# HMTRPBreakoutModule.net
KiCad netlist of a schematic drawn in EAGLE
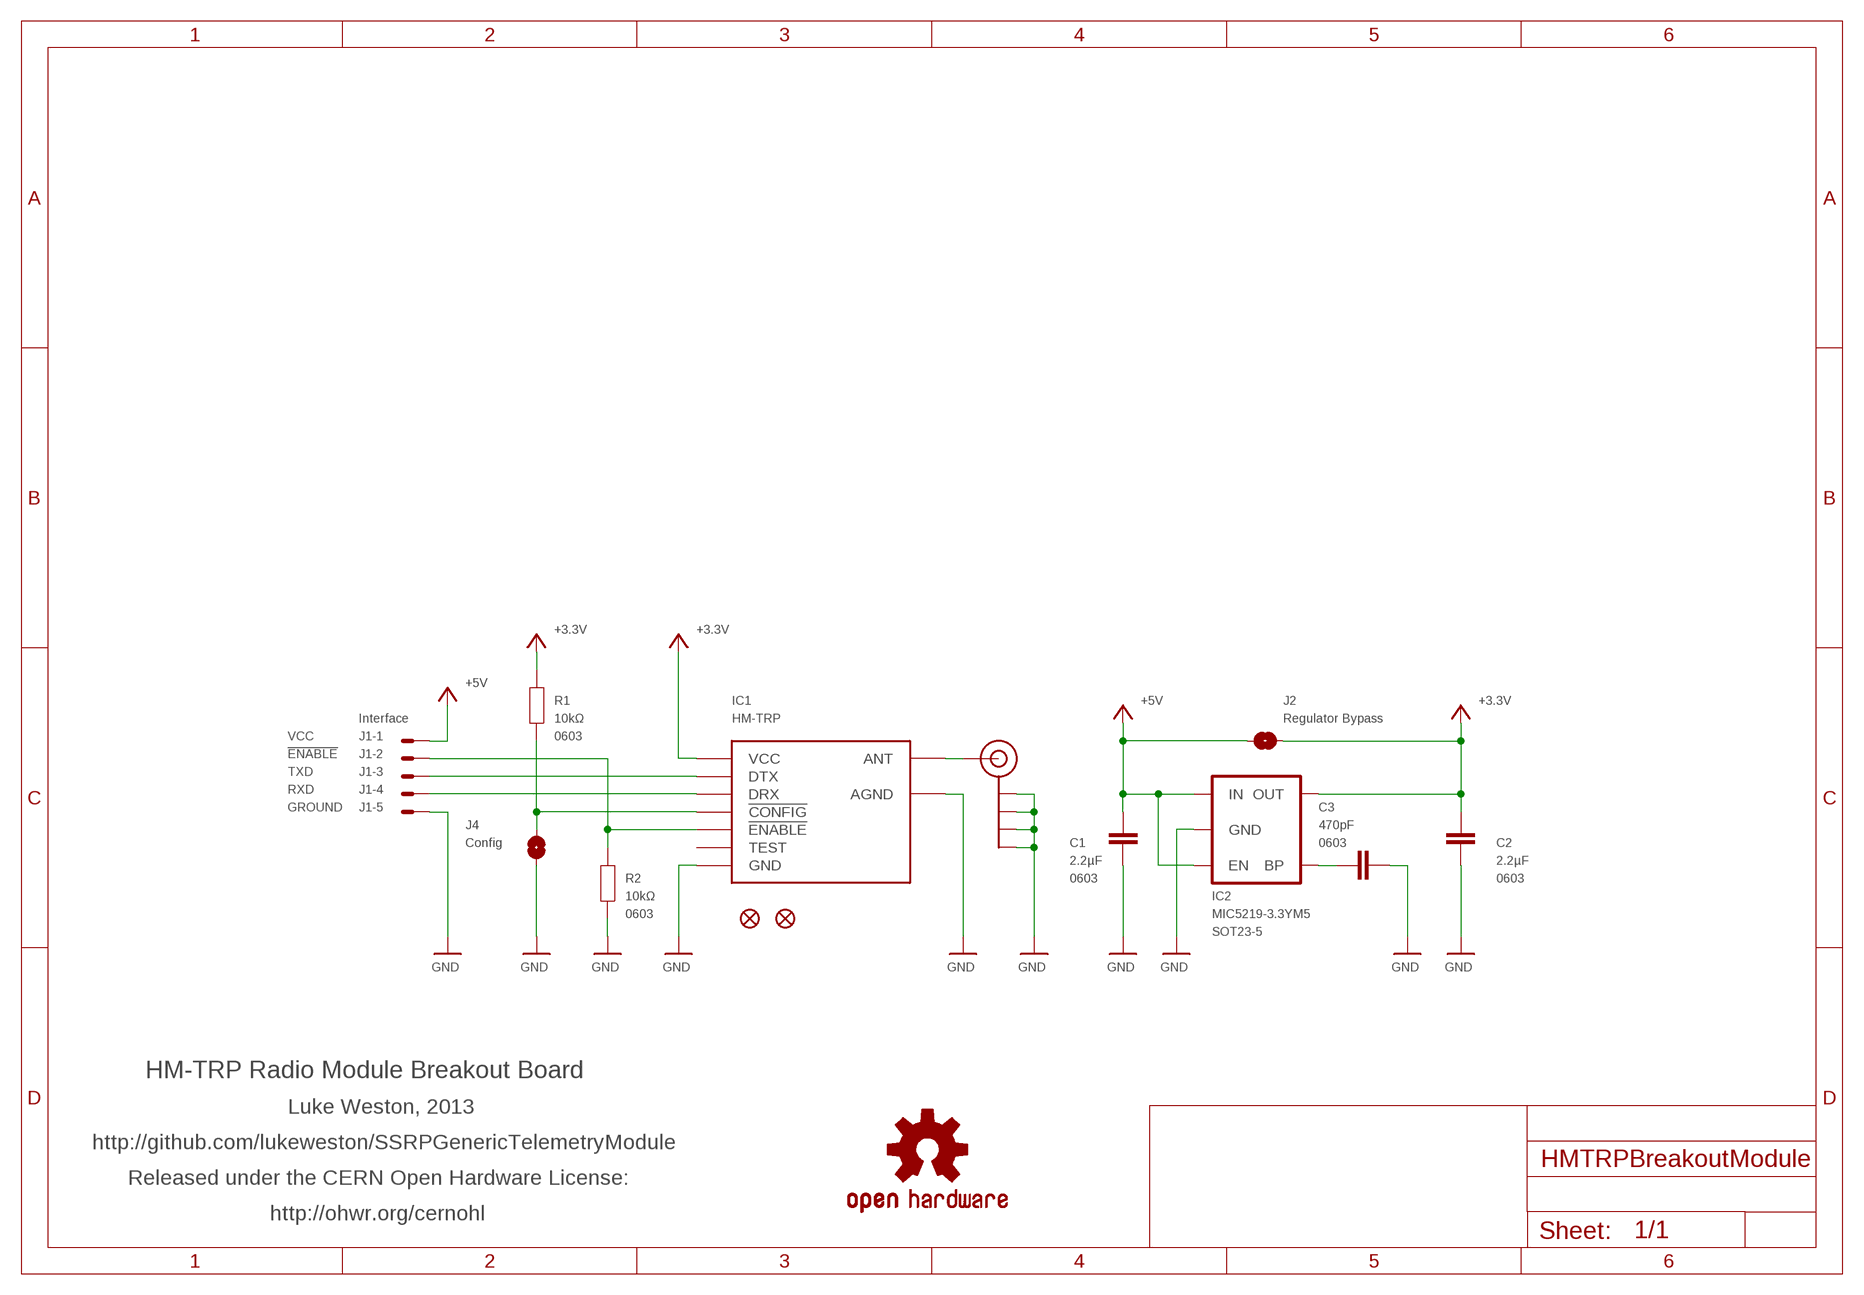
[diagram p0: schematic, sheet 1]

(export (version "E")
  (design (tool "Eeschema 10.0.6"))
  (components
    (comp (ref "C1")
      (value "2.2µF")
      (footprint "eagle-import:0603")
      (fields (field (name "PACKAGE") "0603"))
      (libsource (lib "eagle-import") (part "CAP0603"))
    )
    (comp (ref "C2")
      (value "2.2µF")
      (footprint "eagle-import:0603")
      (fields (field (name "PACKAGE") "0603"))
      (libsource (lib "eagle-import") (part "CAP0603"))
    )
    (comp (ref "C3")
      (value "470pF")
      (footprint "eagle-import:0603")
      (fields (field (name "PACKAGE") "0603"))
      (libsource (lib "eagle-import") (part "CAP0603"))
    )
    (comp (ref "IC1")
      (value "HM-TRP")
      (footprint "eagle-import:HM-TRP-SMD")
      (libsource (lib "eagle-import") (part "HM-TRPSMD"))
    )
    (comp (ref "IC2")
      (value "MIC5219-3.3YM5")
      (footprint "eagle-import:SOT23-5")
      (fields (field (name "PACKAGE") "SOT23-5"))
      (libsource (lib "eagle-import") (part "V_REG_LDOSMD"))
    )
    (comp (ref "J1")
      (value "Interface")
      (footprint "eagle-import:22-23-2051")
      (fields (field (name "MF") "MOLEX") (field (name "MPN") "22-23-2051"))
      (libsource (lib "eagle-import") (part "22-23-2051"))
    )
    (comp (ref "J2")
      (value "Regulator Bypass")
      (footprint "eagle-import:SJ")
      (libsource (lib "eagle-import") (part "SJ"))
    )
    (comp (ref "J3")
      (value "Antenna")
      (footprint "eagle-import:SMA-EDGE")
      (libsource (lib "eagle-import") (part "SMA_EDGE"))
    )
    (comp (ref "J4")
      (value "Config")
      (footprint "eagle-import:SJ")
      (libsource (lib "eagle-import") (part "SJ"))
    )
    (comp (ref "JP1")
      (value "FIDUCIAL1X2")
      (footprint "eagle-import:FIDUCIAL-1X2")
      (libsource (lib "eagle-import") (part "FIDUCIAL1X2"))
    )
    (comp (ref "JP2")
      (value "FIDUCIAL1X2")
      (footprint "eagle-import:FIDUCIAL-1X2")
      (libsource (lib "eagle-import") (part "FIDUCIAL1X2"))
    )
    (comp (ref "R1")
      (value "10kΩ")
      (footprint "eagle-import:0603")
      (fields (field (name "PACKAGE") "0603"))
      (libsource (lib "eagle-import") (part "RESISTOR0603"))
    )
    (comp (ref "R2")
      (value "10kΩ")
      (footprint "eagle-import:0603")
      (fields (field (name "PACKAGE") "0603"))
      (libsource (lib "eagle-import") (part "RESISTOR0603"))
    )
    (comp (ref "SY")
      (value "OSHW-LOGOS")
      (footprint "eagle-import:OSHW-LOGO-S")
      (libsource (lib "eagle-import") (part "OSHW-LOGOS"))
    )
  )
  (nets
    (net (code "1") (name "+3.3V") (class "Default")
      (node (ref "C2") (pin "1") (pinfunction "1_1") (pintype "passive"))
      (node (ref "IC1") (pin "VCC") (pinfunction "VCC_VCC") (pintype "power_in"))
      (node (ref "IC2") (pin "5") (pinfunction "OUT_5") (pintype "passive"))
      (node (ref "J2") (pin "2") (pinfunction "2_2") (pintype "passive"))
      (node (ref "R1") (pin "1") (pinfunction "1_1") (pintype "passive"))
    )
    (net (code "2") (name "+5V") (class "Default")
      (node (ref "C1") (pin "1") (pinfunction "1_1") (pintype "passive"))
      (node (ref "IC2") (pin "1") (pinfunction "IN_1") (pintype "input"))
      (node (ref "IC2") (pin "3") (pinfunction "EN_3") (pintype "input"))
      (node (ref "J1") (pin "1") (pinfunction "S_1") (pintype "passive"))
      (node (ref "J2") (pin "1") (pinfunction "1_1") (pintype "passive"))
    )
    (net (code "3") (name "GND") (class "Default")
      (node (ref "C1") (pin "2") (pinfunction "2_2") (pintype "passive"))
      (node (ref "C2") (pin "2") (pinfunction "2_2") (pintype "passive"))
      (node (ref "C3") (pin "1") (pinfunction "1_1") (pintype "passive"))
      (node (ref "IC1") (pin "AGND") (pinfunction "AGND_AGND") (pintype "power_in"))
      (node (ref "IC1") (pin "GND") (pinfunction "GND_GND") (pintype "power_in"))
      (node (ref "IC2") (pin "2") (pinfunction "GND_2") (pintype "input"))
      (node (ref "J1") (pin "5") (pinfunction "S_5") (pintype "passive"))
      (node (ref "J3") (pin "GND@0") (pinfunction "GND_GND@0") (pintype "bidirectional"))
      (node (ref "J3") (pin "GND@1") (pinfunction "GND_GND@1") (pintype "bidirectional"))
      (node (ref "J3") (pin "GND@2") (pinfunction "GND_GND@2") (pintype "bidirectional"))
      (node (ref "J3") (pin "GND@3") (pinfunction "GND_GND@3") (pintype "bidirectional"))
      (node (ref "J4") (pin "1") (pinfunction "1_1") (pintype "passive"))
      (node (ref "R2") (pin "2") (pinfunction "2_2") (pintype "passive"))
    )
    (net (code "4") (name "Net-(IC1-~{CONFIG})") (class "Default")
      (node (ref "IC1") (pin "!CONFIG") (pinfunction "~{CONFIG}_!CONFIG") (pintype "input"))
      (node (ref "J4") (pin "2") (pinfunction "2_2") (pintype "passive"))
      (node (ref "R1") (pin "2") (pinfunction "2_2") (pintype "passive"))
    )
    (net (code "5") (name "Net-(IC1-~{ENABLE})") (class "Default")
      (node (ref "IC1") (pin "!ENABLE") (pinfunction "~{ENABLE}_!ENABLE") (pintype "input"))
      (node (ref "J1") (pin "2") (pinfunction "S_2") (pintype "passive"))
      (node (ref "R2") (pin "1") (pinfunction "1_1") (pintype "passive"))
    )
    (net (code "6") (name "Net-(IC2-BP)") (class "Default")
      (node (ref "C3") (pin "2") (pinfunction "2_2") (pintype "passive"))
      (node (ref "IC2") (pin "4") (pinfunction "BP_4") (pintype "input"))
    )
    (net (code "7") (name "Net-(J1C-S)") (class "Default")
      (node (ref "IC1") (pin "DTX") (pinfunction "DTX_DTX") (pintype "output"))
      (node (ref "J1") (pin "3") (pinfunction "S_3") (pintype "passive"))
    )
    (net (code "8") (name "Net-(J1D-S)") (class "Default")
      (node (ref "IC1") (pin "DRX") (pinfunction "DRX_DRX") (pintype "input"))
      (node (ref "J1") (pin "4") (pinfunction "S_4") (pintype "passive"))
    )
    (net (code "9") (name "Net-(J3-SIGNAL)") (class "Default")
      (node (ref "IC1") (pin "ANT") (pinfunction "ANT_ANT") (pintype "bidirectional"))
      (node (ref "J3") (pin "SIG") (pinfunction "SIGNAL_SIG") (pintype "bidirectional"))
    )
    (net (code "10") (name "unconnected-(IC1-PadTEST)") (class "Default")
      (node (ref "IC1") (pin "TEST") (pinfunction "TEST_TEST") (pintype "no_connect"))
    )
  )
)
